# 06_USB_Type-C_DFP.net
KiCad netlist of a schematic drawn in Altium Designer
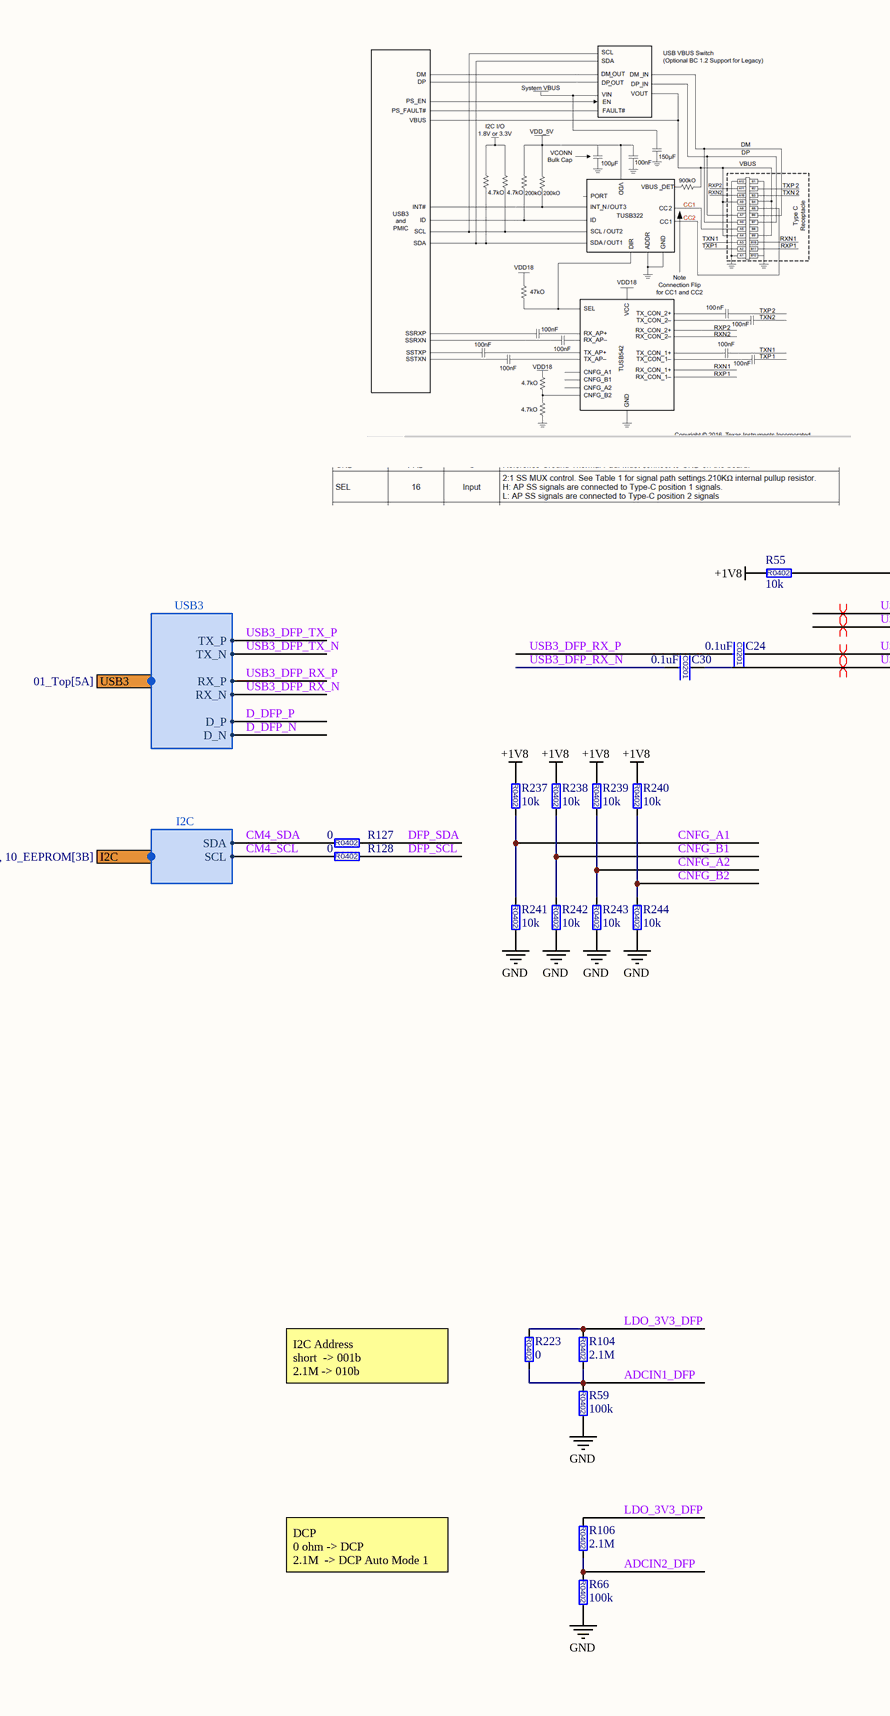
[diagram p0: 06_USB_Type-C_DFP.SchDoc, left]
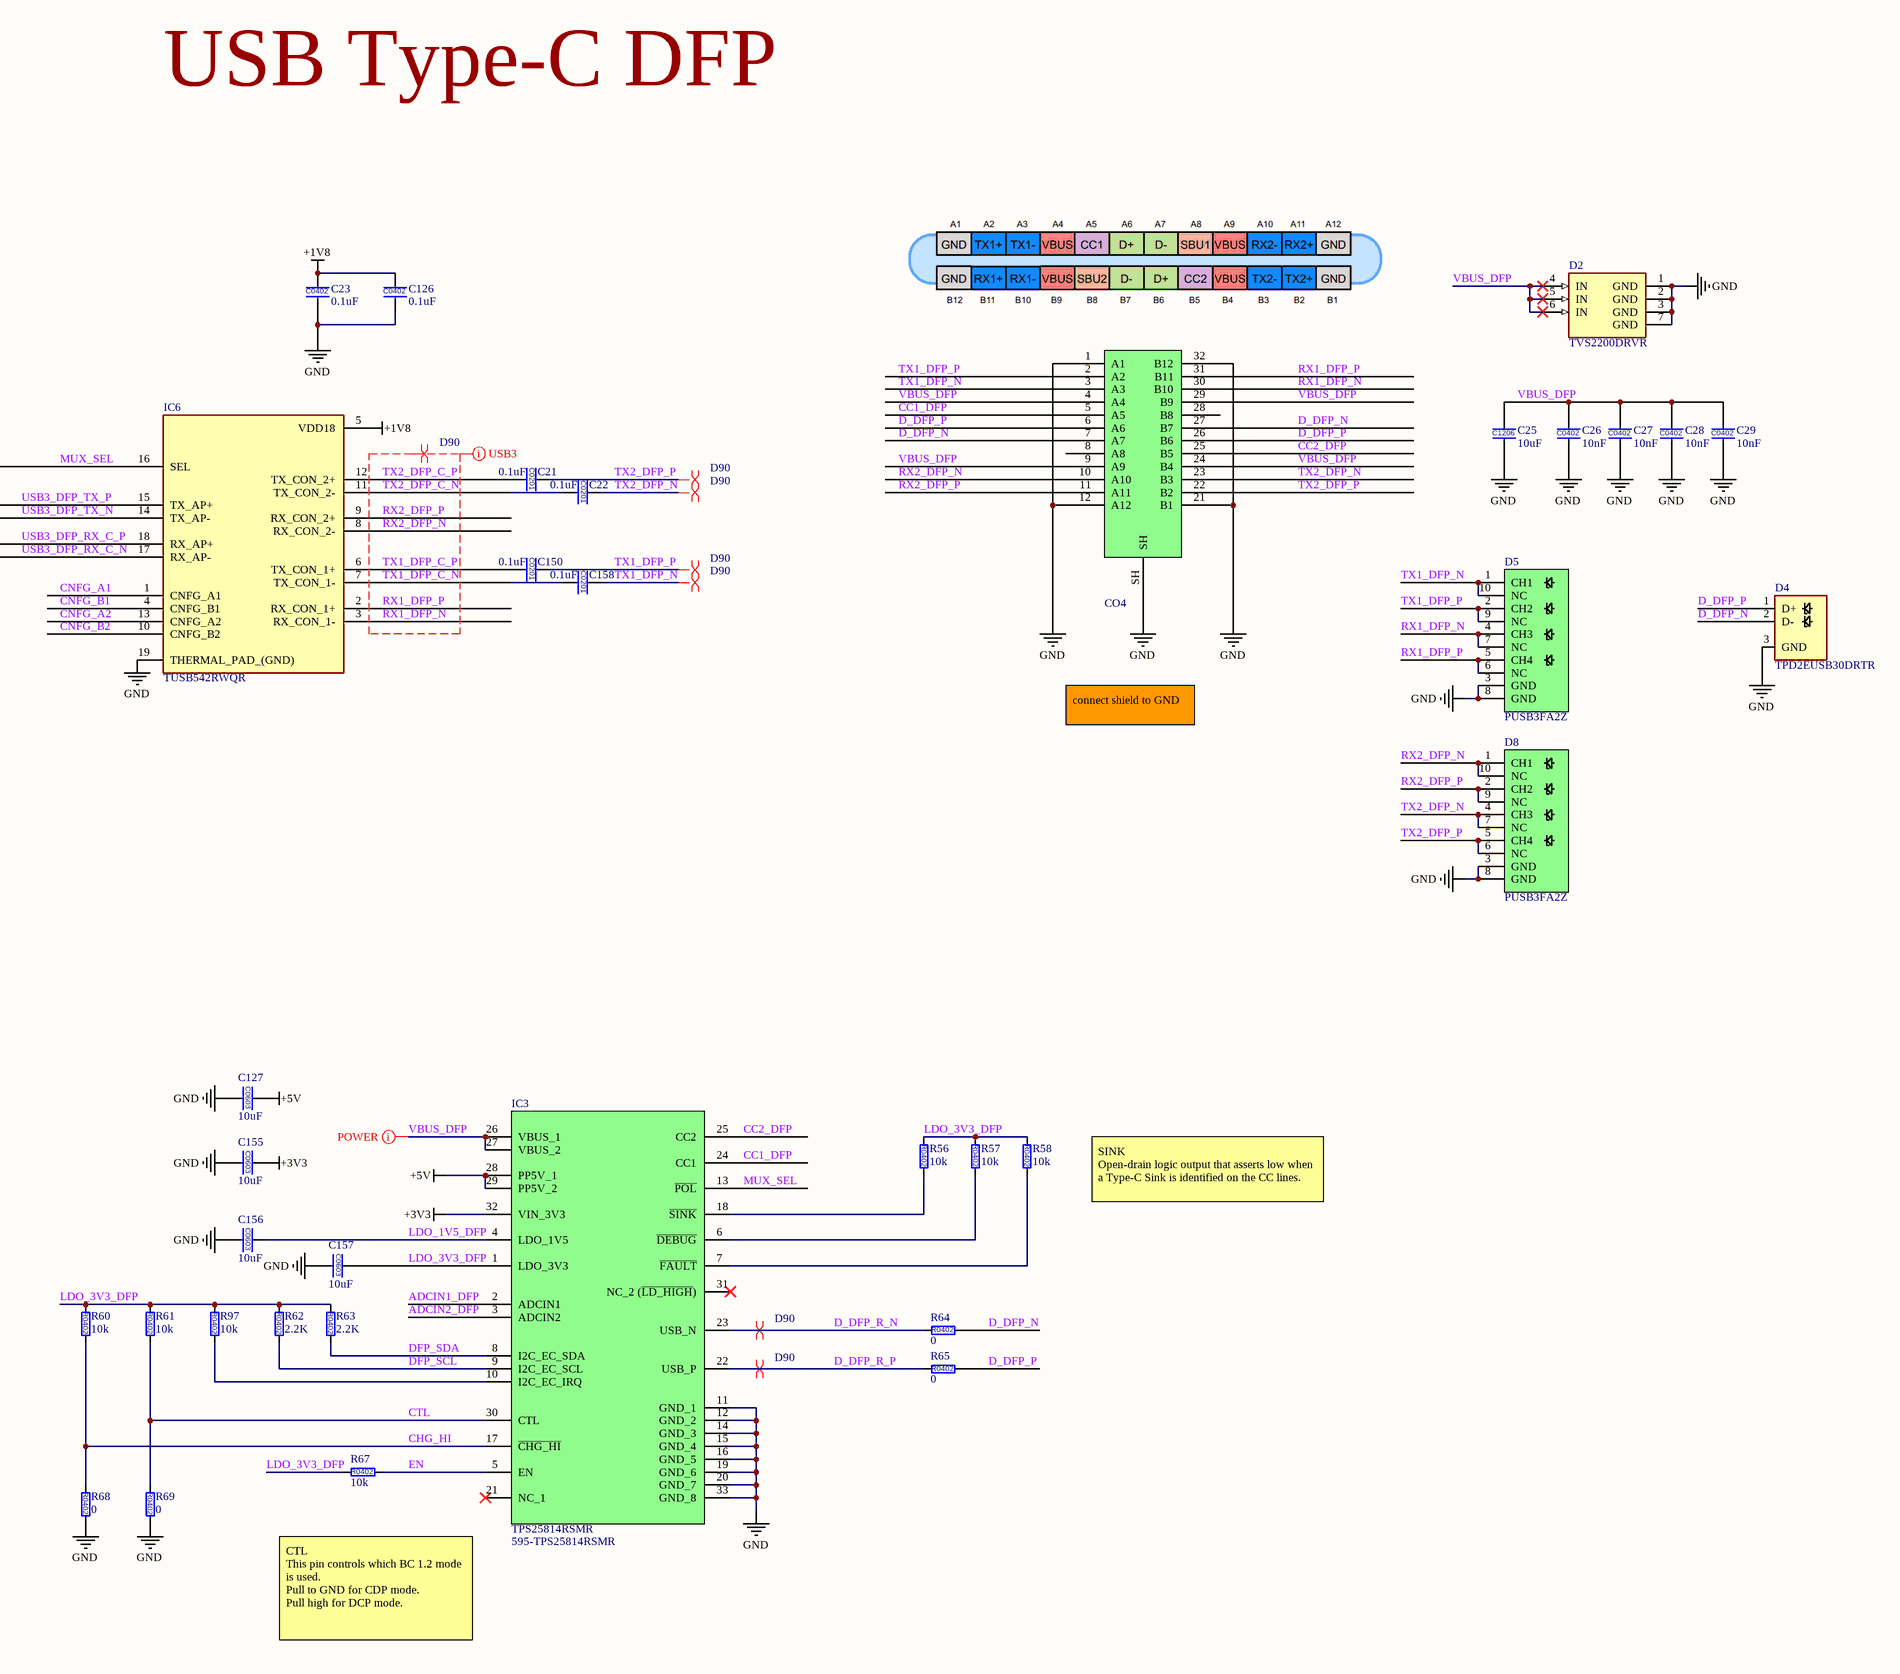
[diagram p1: 06_USB_Type-C_DFP.SchDoc, right]

(export (version "E")
  (design (tool "Eeschema 10.0.6"))
  (components
    (comp (ref "C21")
      (value "0.1uF")
      (footprint "C0201")
      (description "CAP CER  0.1uF 10% 6.3V X5R 0201")
      (fields
        (field (name "MANUFACTURER") "AVX Corporation")
        (field (name "MANUFACTURER PART NUMBER") "02016D104KAT")
      )
      (libsource (lib "Capacitor") (part "02016D104KAT"))
    )
    (comp (ref "C22")
      (value "0.1uF")
      (footprint "C0201")
      (description "CAP CER  0.1uF 10% 6.3V X5R 0201")
      (fields
        (field (name "MANUFACTURER") "AVX Corporation")
        (field (name "MANUFACTURER PART NUMBER") "02016D104KAT")
      )
      (libsource (lib "Capacitor") (part "02016D104KAT"))
    )
    (comp (ref "C23")
      (value "0.1uF")
      (footprint "C0402")
      (description "CAP CER  0.1uF 10% 25V X5R 0402")
      (fields
        (field (name "MANUFACTURER") "AVX Corporation")
        (field (name "MANUFACTURER PART NUMBER") "04023D104KAT2A")
      )
      (libsource (lib "Capacitor") (part "04023D104KAT2A"))
    )
    (comp (ref "C24")
      (value "0.1uF")
      (footprint "C0201")
      (description "CAP CER  0.1uF 10% 6.3V X5R 0201")
      (fields
        (field (name "MANUFACTURER") "AVX Corporation")
        (field (name "MANUFACTURER PART NUMBER") "02016D104KAT")
      )
      (libsource (lib "Capacitor") (part "02016D104KAT"))
    )
    (comp (ref "C25")
      (value "10uF")
      (footprint "C1206")
      (description "CAP CER  10uF 10% 50V X5R 1206")
      (fields
        (field (name "MANUFACTURER") "KYOCERA AVX")
        (field (name "MANUFACTURER PART NUMBER") "12065D106KAT4A")
      )
      (libsource (lib "Capacitor") (part "12065D106KAT4A"))
    )
    (comp (ref "C26")
      (value "10nF")
      (footprint "C0402")
      (description "CAP CER 10nF 5% 50V X7R 0402")
      (fields
        (field (name "MANUFACTURER") "KYOCERA AVX")
        (field (name "MANUFACTURER PART NUMBER") "04025C103JAT2A")
      )
      (libsource (lib "Capacitor") (part "04025C103JAT2A"))
    )
    (comp (ref "C27")
      (value "10nF")
      (footprint "C0402")
      (description "CAP CER 10nF 5% 50V X7R 0402")
      (fields
        (field (name "MANUFACTURER") "KYOCERA AVX")
        (field (name "MANUFACTURER PART NUMBER") "04025C103JAT2A")
      )
      (libsource (lib "Capacitor") (part "04025C103JAT2A"))
    )
    (comp (ref "C28")
      (value "10nF")
      (footprint "C0402")
      (description "CAP CER 10nF 5% 50V X7R 0402")
      (fields
        (field (name "MANUFACTURER") "KYOCERA AVX")
        (field (name "MANUFACTURER PART NUMBER") "04025C103JAT2A")
      )
      (libsource (lib "Capacitor") (part "04025C103JAT2A"))
    )
    (comp (ref "C29")
      (value "10nF")
      (footprint "C0402")
      (description "CAP CER 10nF 5% 50V X7R 0402")
      (fields
        (field (name "MANUFACTURER") "KYOCERA AVX")
        (field (name "MANUFACTURER PART NUMBER") "04025C103JAT2A")
      )
      (libsource (lib "Capacitor") (part "04025C103JAT2A"))
    )
    (comp (ref "C30")
      (value "0.1uF")
      (footprint "C0201")
      (description "CAP CER  0.1uF 10% 6.3V X5R 0201")
      (fields
        (field (name "MANUFACTURER") "AVX Corporation")
        (field (name "MANUFACTURER PART NUMBER") "02016D104KAT")
      )
      (libsource (lib "Capacitor") (part "02016D104KAT"))
    )
    (comp (ref "C126")
      (value "0.1uF")
      (footprint "C0402")
      (description "CAP CER  0.1uF 10% 25V X5R 0402")
      (fields
        (field (name "MANUFACTURER") "AVX Corporation")
        (field (name "MANUFACTURER PART NUMBER") "04023D104KAT2A")
      )
      (libsource (lib "Capacitor") (part "04023D104KAT2A"))
    )
    (comp (ref "C127")
      (value "10uF")
      (footprint "C0603")
      (description "CAP CER 10uF 10% 10V X5R 0603")
      (fields
        (field (name "MANUFACTURER") "KYOCERA AVX")
        (field (name "MANUFACTURER PART NUMBER") "0603ZD106KAT2A")
      )
      (libsource (lib "Capacitor") (part "0603ZD106KAT2A"))
    )
    (comp (ref "C150")
      (value "0.1uF")
      (footprint "C0201")
      (description "CAP CER  0.1uF 10% 6.3V X5R 0201")
      (fields
        (field (name "MANUFACTURER") "AVX Corporation")
        (field (name "MANUFACTURER PART NUMBER") "02016D104KAT")
      )
      (libsource (lib "Capacitor") (part "02016D104KAT"))
    )
    (comp (ref "C155")
      (value "10uF")
      (footprint "C0603")
      (description "CAP CER 10uF 10% 10V X5R 0603")
      (fields
        (field (name "MANUFACTURER") "KYOCERA AVX")
        (field (name "MANUFACTURER PART NUMBER") "0603ZD106KAT2A")
      )
      (libsource (lib "Capacitor") (part "0603ZD106KAT2A"))
    )
    (comp (ref "C156")
      (value "10uF")
      (footprint "C0603")
      (description "CAP CER 10uF 10% 10V X5R 0603")
      (fields
        (field (name "MANUFACTURER") "KYOCERA AVX")
        (field (name "MANUFACTURER PART NUMBER") "0603ZD106KAT2A")
      )
      (libsource (lib "Capacitor") (part "0603ZD106KAT2A"))
    )
    (comp (ref "C157")
      (value "10uF")
      (footprint "C0603")
      (description "CAP CER 10uF 10% 10V X5R 0603")
      (fields
        (field (name "MANUFACTURER") "KYOCERA AVX")
        (field (name "MANUFACTURER PART NUMBER") "0603ZD106KAT2A")
      )
      (libsource (lib "Capacitor") (part "0603ZD106KAT2A"))
    )
    (comp (ref "C158")
      (value "0.1uF")
      (footprint "C0201")
      (description "CAP CER  0.1uF 10% 6.3V X5R 0201")
      (fields
        (field (name "MANUFACTURER") "AVX Corporation")
        (field (name "MANUFACTURER PART NUMBER") "02016D104KAT")
      )
      (libsource (lib "Capacitor") (part "02016D104KAT"))
    )
    (comp (ref "CO4")
      (value "USB4070-30-C")
      (footprint "USB4070-30-C")
      (description "24 Position 20 VDC USB Type C Horizontal USB 3.1 Receptacle Connector")
      (fields
        (field (name "PART NUMBER") "CO0021")
        (field (name "MANUFACTURER") "Global Connector Technology")
      )
      (libsource (lib "new") (part "USB4070-30-C"))
    )
    (comp (ref "D2")
      (value "TVS2200DRVR")
      (footprint "TVS2200D_SON_6")
      (description "22-V flat-clamp surge protection device 6-WSON -40 to 125")
      (fields
        (field (name "OCTOPART") "https://octopart.com/tvs2200drvr-texas+instruments-88217346")
        (field (name "MANUFACTURER") "Texas Instruments")
      )
      (libsource (lib "new") (part "TVS2200DRVR"))
    )
    (comp (ref "D4")
      (value "TPD2EUSB30DRTR")
      (footprint "TPD2EUSB30DRTR_SOT-3")
      (fields (field (name "MANUFACTURER") "Texas Instruments"))
      (libsource (lib "TVS") (part "TPD2EUSB30DRTR"))
    )
    (comp (ref "D5")
      (value "PUSB3FA2Z")
      (footprint "PUSB3FA2Z_DFN_2510_10")
      (description "PUSB3FA2/SOT1176/XSON10")
      (fields (field (name "PART NUMBER") "DI0007") (field (name "MANUFACTURER") "Nexperia"))
      (libsource (lib "new") (part "PUSB3FA2Z"))
    )
    (comp (ref "D8")
      (value "PUSB3FA2Z")
      (footprint "PUSB3FA2Z_DFN_2510_10")
      (description "PUSB3FA2/SOT1176/XSON10")
      (fields (field (name "PART NUMBER") "DI0007") (field (name "MANUFACTURER") "Nexperia"))
      (libsource (lib "new") (part "PUSB3FA2Z"))
    )
    (comp (ref "IC3")
      (value "TPS25814RSMR")
      (footprint "TPS25814RSMR_VQFN_32")
      (description "USB Type-C® controller with integrated source power switch 32-VQFN -40 to 105")
      (fields
        (field (name "MOUSER PART NUMBER") "595-TPS25814RSMR")
        (field (name "MANUFACTURER") "Texas Instruments")
        (field (name "SUPPLIER PART NUMBER 1") "595-TPS25814RSMR")
      )
      (libsource (lib "new") (part "TPS25814RSMR"))
    )
    (comp (ref "IC6")
      (value "TUSB542RWQR")
      (footprint "TUSB542_X2QFN_18")
      (description "Integrated Circuit")
      (fields (field (name "MOUSER PART NUMBER") "595-TUSB542RWQR"))
      (libsource (lib "ic") (part "TUSB542RWQR"))
    )
    (comp (ref "R55")
      (value "10k")
      (footprint "R0402")
      (description "RES SMD 10K ohm 1% 1/16W R0402")
      (fields
        (field (name "MANUFACTURER") "Vishay")
        (field (name "MANUFACTURER PART NUMBER") "CRCW040210K0FK")
      )
      (libsource (lib "Resistor") (part "CRCW040210K0FK"))
    )
    (comp (ref "R56")
      (value "10k")
      (footprint "R0402")
      (description "RES SMD 10K ohm 1% 1/16W R0402")
      (fields
        (field (name "MANUFACTURER") "Vishay")
        (field (name "MANUFACTURER PART NUMBER") "CRCW040210K0FK")
      )
      (libsource (lib "Resistor") (part "CRCW040210K0FK"))
    )
    (comp (ref "R57")
      (value "10k")
      (footprint "R0402")
      (description "RES SMD 10K ohm 1% 1/16W R0402")
      (fields
        (field (name "MANUFACTURER") "Vishay")
        (field (name "MANUFACTURER PART NUMBER") "CRCW040210K0FK")
      )
      (libsource (lib "Resistor") (part "CRCW040210K0FK"))
    )
    (comp (ref "R58")
      (value "10k")
      (footprint "R0402")
      (description "RES SMD 10K ohm 1% 1/16W R0402")
      (fields
        (field (name "MANUFACTURER") "Vishay")
        (field (name "MANUFACTURER PART NUMBER") "CRCW040210K0FK")
      )
      (libsource (lib "Resistor") (part "CRCW040210K0FK"))
    )
    (comp (ref "R59")
      (value "100k")
      (footprint "R0402")
      (description "RES SMD 100K ohm 1% 1/16W R0402")
      (fields
        (field (name "MANUFACTURER") "Vishay")
        (field (name "MANUFACTURER PART NUMBER") "CRCW0402100KFKEDC")
      )
      (libsource (lib "Resistor") (part "CRCW0402100KFKEDC"))
    )
    (comp (ref "R60")
      (value "10k")
      (footprint "R0402")
      (description "RES SMD 10K ohm 1% 1/16W R0402")
      (fields
        (field (name "MANUFACTURER") "Vishay")
        (field (name "MANUFACTURER PART NUMBER") "CRCW040210K0FK")
      )
      (libsource (lib "Resistor") (part "CRCW040210K0FK"))
    )
    (comp (ref "R61")
      (value "10k")
      (footprint "R0402")
      (description "RES SMD 10K ohm 1% 1/16W R0402")
      (fields
        (field (name "MANUFACTURER") "Vishay")
        (field (name "MANUFACTURER PART NUMBER") "CRCW040210K0FK")
      )
      (libsource (lib "Resistor") (part "CRCW040210K0FK"))
    )
    (comp (ref "R62")
      (value "2.2K")
      (footprint "R0402")
      (description "RES SMD 2.2K ohm 1% 1/16W R0402")
      (fields
        (field (name "MANUFACTURER") "Vishay")
        (field (name "MANUFACTURER PART NUMBER") "CRCW04022K20FK")
      )
      (libsource (lib "Resistor") (part "CRCW04022K20FK"))
    )
    (comp (ref "R63")
      (value "2.2K")
      (footprint "R0402")
      (description "RES SMD 2.2K ohm 1% 1/16W R0402")
      (fields
        (field (name "MANUFACTURER") "Vishay")
        (field (name "MANUFACTURER PART NUMBER") "CRCW04022K20FK")
      )
      (libsource (lib "Resistor") (part "CRCW04022K20FK"))
    )
    (comp (ref "R64")
      (value "0")
      (footprint "R0402")
      (description "RES SMD 0 ohm 1/16W R0402")
      (fields
        (field (name "MANUFACTURER") "Vishay Dale")
        (field (name "MANUFACTURER PART NUMBER") "CRCW04020000Z0")
      )
      (libsource (lib "Resistor") (part "CRCW04020000Z0"))
    )
    (comp (ref "R65")
      (value "0")
      (footprint "R0402")
      (description "RES SMD 0 ohm 1/16W R0402")
      (fields
        (field (name "MANUFACTURER") "Vishay Dale")
        (field (name "MANUFACTURER PART NUMBER") "CRCW04020000Z0")
      )
      (libsource (lib "Resistor") (part "CRCW04020000Z0"))
    )
    (comp (ref "R66")
      (value "100k")
      (footprint "R0402")
      (description "RES SMD 100K ohm 1% 1/16W R0402")
      (fields
        (field (name "MANUFACTURER") "Vishay")
        (field (name "MANUFACTURER PART NUMBER") "CRCW0402100KFKEDC")
      )
      (libsource (lib "Resistor") (part "CRCW0402100KFKEDC"))
    )
    (comp (ref "R67")
      (value "10k")
      (footprint "R0402")
      (description "RES SMD 10K ohm 1% 1/16W R0402")
      (fields
        (field (name "MANUFACTURER") "Vishay")
        (field (name "MANUFACTURER PART NUMBER") "CRCW040210K0FK")
      )
      (libsource (lib "Resistor") (part "CRCW040210K0FK"))
    )
    (comp (ref "R68")
      (value "0")
      (footprint "R0402")
      (description "RES SMD 0 ohm 1/16W R0402")
      (fields
        (field (name "MANUFACTURER") "Vishay Dale")
        (field (name "MANUFACTURER PART NUMBER") "CRCW04020000Z0")
      )
      (libsource (lib "Resistor") (part "CRCW04020000Z0"))
    )
    (comp (ref "R69")
      (value "0")
      (footprint "R0402")
      (description "RES SMD 0 ohm 1/16W R0402")
      (fields
        (field (name "MANUFACTURER") "Vishay Dale")
        (field (name "MANUFACTURER PART NUMBER") "CRCW04020000Z0")
      )
      (libsource (lib "Resistor") (part "CRCW04020000Z0"))
    )
    (comp (ref "R97")
      (value "10k")
      (footprint "R0402")
      (description "RES SMD 10K ohm 1% 1/16W R0402")
      (fields
        (field (name "MANUFACTURER") "Vishay")
        (field (name "MANUFACTURER PART NUMBER") "CRCW040210K0FK")
      )
      (libsource (lib "Resistor") (part "CRCW040210K0FK"))
    )
    (comp (ref "R104")
      (value "2.1M")
      (footprint "R0402")
      (description "RES SMD 2.1M ohm 1% 1/16W R0402")
      (fields
        (field (name "MANUFACTURER") "Vishay")
        (field (name "MANUFACTURER PART NUMBER") "CRCW04022M10FKED")
      )
      (libsource (lib "Resistor") (part "CRCW04022M10FKED"))
    )
    (comp (ref "R106")
      (value "2.1M")
      (footprint "R0402")
      (description "RES SMD 2.1M ohm 1% 1/16W R0402")
      (fields
        (field (name "MANUFACTURER") "Vishay")
        (field (name "MANUFACTURER PART NUMBER") "CRCW04022M10FKED")
      )
      (libsource (lib "Resistor") (part "CRCW04022M10FKED"))
    )
    (comp (ref "R127")
      (value "0")
      (footprint "R0402")
      (description "RES SMD 0 ohm 1/16W R0402")
      (fields
        (field (name "MANUFACTURER") "Vishay Dale")
        (field (name "MANUFACTURER PART NUMBER") "CRCW04020000Z0")
      )
      (libsource (lib "Resistor") (part "CRCW04020000Z0"))
    )
    (comp (ref "R128")
      (value "0")
      (footprint "R0402")
      (description "RES SMD 0 ohm 1/16W R0402")
      (fields
        (field (name "MANUFACTURER") "Vishay Dale")
        (field (name "MANUFACTURER PART NUMBER") "CRCW04020000Z0")
      )
      (libsource (lib "Resistor") (part "CRCW04020000Z0"))
    )
    (comp (ref "R223")
      (value "0")
      (footprint "R0402")
      (description "RES SMD 0 ohm 1/16W R0402")
      (fields
        (field (name "MANUFACTURER") "Vishay Dale")
        (field (name "MANUFACTURER PART NUMBER") "CRCW04020000Z0")
      )
      (libsource (lib "Resistor") (part "CRCW04020000Z0"))
    )
    (comp (ref "R237")
      (value "10k")
      (footprint "R0402")
      (description "RES SMD 10K ohm 1% 1/16W R0402")
      (fields
        (field (name "MANUFACTURER") "Vishay")
        (field (name "MANUFACTURER PART NUMBER") "CRCW040210K0FK")
      )
      (libsource (lib "Resistor") (part "CRCW040210K0FK"))
    )
    (comp (ref "R238")
      (value "10k")
      (footprint "R0402")
      (description "RES SMD 10K ohm 1% 1/16W R0402")
      (fields
        (field (name "MANUFACTURER") "Vishay")
        (field (name "MANUFACTURER PART NUMBER") "CRCW040210K0FK")
      )
      (libsource (lib "Resistor") (part "CRCW040210K0FK"))
    )
    (comp (ref "R239")
      (value "10k")
      (footprint "R0402")
      (description "RES SMD 10K ohm 1% 1/16W R0402")
      (fields
        (field (name "MANUFACTURER") "Vishay")
        (field (name "MANUFACTURER PART NUMBER") "CRCW040210K0FK")
      )
      (libsource (lib "Resistor") (part "CRCW040210K0FK"))
    )
    (comp (ref "R240")
      (value "10k")
      (footprint "R0402")
      (description "RES SMD 10K ohm 1% 1/16W R0402")
      (fields
        (field (name "MANUFACTURER") "Vishay")
        (field (name "MANUFACTURER PART NUMBER") "CRCW040210K0FK")
      )
      (libsource (lib "Resistor") (part "CRCW040210K0FK"))
    )
    (comp (ref "R241")
      (value "10k")
      (footprint "R0402")
      (description "RES SMD 10K ohm 1% 1/16W R0402")
      (fields
        (field (name "MANUFACTURER") "Vishay")
        (field (name "MANUFACTURER PART NUMBER") "CRCW040210K0FK")
      )
      (libsource (lib "Resistor") (part "CRCW040210K0FK"))
    )
    (comp (ref "R242")
      (value "10k")
      (footprint "R0402")
      (description "RES SMD 10K ohm 1% 1/16W R0402")
      (fields
        (field (name "MANUFACTURER") "Vishay")
        (field (name "MANUFACTURER PART NUMBER") "CRCW040210K0FK")
      )
      (libsource (lib "Resistor") (part "CRCW040210K0FK"))
    )
    (comp (ref "R243")
      (value "10k")
      (footprint "R0402")
      (description "RES SMD 10K ohm 1% 1/16W R0402")
      (fields
        (field (name "MANUFACTURER") "Vishay")
        (field (name "MANUFACTURER PART NUMBER") "CRCW040210K0FK")
      )
      (libsource (lib "Resistor") (part "CRCW040210K0FK"))
    )
    (comp (ref "R244")
      (value "10k")
      (footprint "R0402")
      (description "RES SMD 10K ohm 1% 1/16W R0402")
      (fields
        (field (name "MANUFACTURER") "Vishay")
        (field (name "MANUFACTURER PART NUMBER") "CRCW040210K0FK")
      )
      (libsource (lib "Resistor") (part "CRCW040210K0FK"))
    )
  )
  (nets
    (net (code "3") (name "+1V8") (class "Default")
      (node (ref "C126") (pin "1") (pinfunction "1_1") (pintype "passive"))
      (node (ref "C23") (pin "1") (pinfunction "1_1") (pintype "passive"))
      (node (ref "IC6") (pin "5") (pinfunction "VDD18_5") (pintype "passive"))
      (node (ref "R237") (pin "1") (pinfunction "1_1") (pintype "passive"))
      (node (ref "R238") (pin "1") (pinfunction "1_1") (pintype "passive"))
      (node (ref "R239") (pin "1") (pinfunction "1_1") (pintype "passive"))
      (node (ref "R240") (pin "1") (pinfunction "1_1") (pintype "passive"))
      (node (ref "R55") (pin "1") (pinfunction "1_1") (pintype "passive"))
    )
    (net (code "4") (name "+3V3") (class "Default")
      (node (ref "C155") (pin "1") (pinfunction "1_1") (pintype "passive"))
      (node (ref "IC3") (pin "32") (pinfunction "VIN_3V3_32") (pintype "passive"))
    )
    (net (code "5") (name "+5V") (class "Default")
      (node (ref "C127") (pin "1") (pinfunction "1_1") (pintype "passive"))
      (node (ref "IC3") (pin "28") (pinfunction "PP5V_1_28") (pintype "passive"))
      (node (ref "IC3") (pin "29") (pinfunction "PP5V_2_29") (pintype "passive"))
    )
    (net (code "6") (name "/ADCIN1_DFP") (class "Default")
      (node (ref "IC3") (pin "2") (pinfunction "ADCIN1_2") (pintype "passive"))
      (node (ref "R104") (pin "2") (pinfunction "2_2") (pintype "passive"))
      (node (ref "R223") (pin "2") (pinfunction "2_2") (pintype "passive"))
      (node (ref "R59") (pin "1") (pinfunction "1_1") (pintype "passive"))
    )
    (net (code "7") (name "/ADCIN2_DFP") (class "Default")
      (node (ref "IC3") (pin "3") (pinfunction "ADCIN2_3") (pintype "passive"))
      (node (ref "R106") (pin "2") (pinfunction "2_2") (pintype "passive"))
      (node (ref "R66") (pin "1") (pinfunction "1_1") (pintype "passive"))
    )
    (net (code "8") (name "/CC1_DFP") (class "Default")
      (node (ref "CO4") (pin "5") (pinfunction "A5_5") (pintype "passive"))
      (node (ref "IC3") (pin "24") (pinfunction "CC1_24") (pintype "passive"))
    )
    (net (code "9") (name "/CC2_DFP") (class "Default")
      (node (ref "CO4") (pin "25") (pinfunction "B5_25") (pintype "passive"))
      (node (ref "IC3") (pin "25") (pinfunction "CC2_25") (pintype "passive"))
    )
    (net (code "10") (name "/CHG_HI") (class "Default")
      (node (ref "IC3") (pin "17") (pinfunction "~{CHG_HI}_17") (pintype "passive"))
      (node (ref "R60") (pin "2") (pinfunction "2_2") (pintype "passive"))
      (node (ref "R68") (pin "1") (pinfunction "1_1") (pintype "passive"))
    )
    (net (code "11") (name "/CM4_SCL") (class "Default")
      (node (ref "R128") (pin "1") (pinfunction "1_1") (pintype "passive"))
    )
    (net (code "12") (name "/CM4_SDA") (class "Default")
      (node (ref "R127") (pin "1") (pinfunction "1_1") (pintype "passive"))
    )
    (net (code "13") (name "/CNFG_A1") (class "Default")
      (node (ref "IC6") (pin "1") (pinfunction "CNFG_A1_1") (pintype "passive"))
      (node (ref "R237") (pin "2") (pinfunction "2_2") (pintype "passive"))
      (node (ref "R241") (pin "1") (pinfunction "1_1") (pintype "passive"))
    )
    (net (code "14") (name "/CNFG_A2") (class "Default")
      (node (ref "IC6") (pin "13") (pinfunction "CNFG_A2_13") (pintype "passive"))
      (node (ref "R239") (pin "2") (pinfunction "2_2") (pintype "passive"))
      (node (ref "R243") (pin "1") (pinfunction "1_1") (pintype "passive"))
    )
    (net (code "15") (name "/CNFG_B1") (class "Default")
      (node (ref "IC6") (pin "4") (pinfunction "CNFG_B1_4") (pintype "passive"))
      (node (ref "R238") (pin "2") (pinfunction "2_2") (pintype "passive"))
      (node (ref "R242") (pin "1") (pinfunction "1_1") (pintype "passive"))
    )
    (net (code "16") (name "/CNFG_B2") (class "Default")
      (node (ref "IC6") (pin "10") (pinfunction "CNFG_B2_10") (pintype "passive"))
      (node (ref "R240") (pin "2") (pinfunction "2_2") (pintype "passive"))
      (node (ref "R244") (pin "1") (pinfunction "1_1") (pintype "passive"))
    )
    (net (code "17") (name "/CTL") (class "Default")
      (node (ref "IC3") (pin "30") (pinfunction "CTL_30") (pintype "passive"))
      (node (ref "R61") (pin "2") (pinfunction "2_2") (pintype "passive"))
      (node (ref "R69") (pin "1") (pinfunction "1_1") (pintype "passive"))
    )
    (net (code "18") (name "/DFP_SCL") (class "Default")
      (node (ref "IC3") (pin "9") (pinfunction "I2C_EC_SCL_9") (pintype "passive"))
      (node (ref "R128") (pin "2") (pinfunction "2_2") (pintype "passive"))
      (node (ref "R62") (pin "2") (pinfunction "2_2") (pintype "passive"))
    )
    (net (code "19") (name "/DFP_SDA") (class "Default")
      (node (ref "IC3") (pin "8") (pinfunction "I2C_EC_SDA_8") (pintype "passive"))
      (node (ref "R127") (pin "2") (pinfunction "2_2") (pintype "passive"))
      (node (ref "R63") (pin "2") (pinfunction "2_2") (pintype "passive"))
    )
    (net (code "20") (name "/D_DFP_N") (class "Default")
      (node (ref "CO4") (pin "27") (pinfunction "B7_27") (pintype "passive"))
      (node (ref "CO4") (pin "7") (pinfunction "A7_7") (pintype "passive"))
      (node (ref "D4") (pin "2") (pinfunction "D-_2") (pintype "passive"))
      (node (ref "R64") (pin "2") (pinfunction "2_2") (pintype "passive"))
    )
    (net (code "21") (name "/D_DFP_P") (class "Default")
      (node (ref "CO4") (pin "26") (pinfunction "B6_26") (pintype "passive"))
      (node (ref "CO4") (pin "6") (pinfunction "A6_6") (pintype "passive"))
      (node (ref "D4") (pin "1") (pinfunction "D+_1") (pintype "passive"))
      (node (ref "R65") (pin "2") (pinfunction "2_2") (pintype "passive"))
    )
    (net (code "22") (name "/D_DFP_R_N") (class "Default")
      (node (ref "IC3") (pin "23") (pinfunction "USB_N_23") (pintype "passive"))
      (node (ref "R64") (pin "1") (pinfunction "1_1") (pintype "passive"))
    )
    (net (code "23") (name "/D_DFP_R_P") (class "Default")
      (node (ref "IC3") (pin "22") (pinfunction "USB_P_22") (pintype "passive"))
      (node (ref "R65") (pin "1") (pinfunction "1_1") (pintype "passive"))
    )
    (net (code "24") (name "/EN") (class "Default")
      (node (ref "IC3") (pin "5") (pinfunction "EN_5") (pintype "passive"))
      (node (ref "R67") (pin "2") (pinfunction "2_2") (pintype "passive"))
    )
    (net (code "25") (name "/LDO_1V5_DFP") (class "Default")
      (node (ref "C156") (pin "1") (pinfunction "1_1") (pintype "passive"))
      (node (ref "IC3") (pin "4") (pinfunction "LDO_1V5_4") (pintype "passive"))
    )
    (net (code "26") (name "/LDO_3V3_DFP") (class "Default")
      (node (ref "C157") (pin "1") (pinfunction "1_1") (pintype "passive"))
      (node (ref "IC3") (pin "1") (pinfunction "LDO_3V3_1") (pintype "passive"))
      (node (ref "R104") (pin "1") (pinfunction "1_1") (pintype "passive"))
      (node (ref "R106") (pin "1") (pinfunction "1_1") (pintype "passive"))
      (node (ref "R223") (pin "1") (pinfunction "1_1") (pintype "passive"))
      (node (ref "R56") (pin "1") (pinfunction "1_1") (pintype "passive"))
      (node (ref "R57") (pin "1") (pinfunction "1_1") (pintype "passive"))
      (node (ref "R58") (pin "1") (pinfunction "1_1") (pintype "passive"))
      (node (ref "R60") (pin "1") (pinfunction "1_1") (pintype "passive"))
      (node (ref "R61") (pin "1") (pinfunction "1_1") (pintype "passive"))
      (node (ref "R62") (pin "1") (pinfunction "1_1") (pintype "passive"))
      (node (ref "R63") (pin "1") (pinfunction "1_1") (pintype "passive"))
      (node (ref "R67") (pin "1") (pinfunction "1_1") (pintype "passive"))
      (node (ref "R97") (pin "1") (pinfunction "1_1") (pintype "passive"))
    )
    (net (code "27") (name "/MUX_SEL") (class "Default")
      (node (ref "IC3") (pin "13") (pinfunction "~{POL}_13") (pintype "passive"))
      (node (ref "IC6") (pin "16") (pinfunction "SEL_16") (pintype "passive"))
      (node (ref "R55") (pin "2") (pinfunction "2_2") (pintype "passive"))
    )
    (net (code "28") (name "/RX1_DFP_N") (class "Default")
      (node (ref "CO4") (pin "30") (pinfunction "B10_30") (pintype "passive"))
      (node (ref "D5") (pin "4") (pinfunction "CH3_4") (pintype "passive"))
      (node (ref "D5") (pin "7") (pinfunction "NC_7") (pintype "passive"))
      (node (ref "IC6") (pin "3") (pinfunction "RX_CON_1-_3") (pintype "passive"))
    )
    (net (code "29") (name "/RX1_DFP_P") (class "Default")
      (node (ref "CO4") (pin "31") (pinfunction "B11_31") (pintype "passive"))
      (node (ref "D5") (pin "5") (pinfunction "CH4_5") (pintype "passive"))
      (node (ref "D5") (pin "6") (pinfunction "NC_6") (pintype "passive"))
      (node (ref "IC6") (pin "2") (pinfunction "RX_CON_1+_2") (pintype "passive"))
    )
    (net (code "30") (name "/RX2_DFP_N") (class "Default")
      (node (ref "CO4") (pin "10") (pinfunction "A10_10") (pintype "passive"))
      (node (ref "D8") (pin "1") (pinfunction "CH1_1") (pintype "passive"))
      (node (ref "D8") (pin "10") (pinfunction "NC_10") (pintype "passive"))
      (node (ref "IC6") (pin "8") (pinfunction "RX_CON_2-_8") (pintype "passive"))
    )
    (net (code "31") (name "/RX2_DFP_P") (class "Default")
      (node (ref "CO4") (pin "11") (pinfunction "A11_11") (pintype "passive"))
      (node (ref "D8") (pin "2") (pinfunction "CH2_2") (pintype "passive"))
      (node (ref "D8") (pin "9") (pinfunction "NC_9") (pintype "passive"))
      (node (ref "IC6") (pin "9") (pinfunction "RX_CON_2+_9") (pintype "passive"))
    )
    (net (code "32") (name "/TX1_DFP_C_N") (class "Default")
      (node (ref "C158") (pin "2") (pinfunction "2_2") (pintype "passive"))
      (node (ref "IC6") (pin "7") (pinfunction "TX_CON_1-_7") (pintype "passive"))
    )
    (net (code "33") (name "/TX1_DFP_C_P") (class "Default")
      (node (ref "C150") (pin "2") (pinfunction "2_2") (pintype "passive"))
      (node (ref "IC6") (pin "6") (pinfunction "TX_CON_1+_6") (pintype "passive"))
    )
    (net (code "34") (name "/TX1_DFP_N") (class "Default")
      (node (ref "C158") (pin "1") (pinfunction "1_1") (pintype "passive"))
      (node (ref "CO4") (pin "3") (pinfunction "A3_3") (pintype "passive"))
      (node (ref "D5") (pin "1") (pinfunction "CH1_1") (pintype "passive"))
      (node (ref "D5") (pin "10") (pinfunction "NC_10") (pintype "passive"))
    )
    (net (code "35") (name "/TX1_DFP_P") (class "Default")
      (node (ref "C150") (pin "1") (pinfunction "1_1") (pintype "passive"))
      (node (ref "CO4") (pin "2") (pinfunction "A2_2") (pintype "passive"))
      (node (ref "D5") (pin "2") (pinfunction "CH2_2") (pintype "passive"))
      (node (ref "D5") (pin "9") (pinfunction "NC_9") (pintype "passive"))
    )
    (net (code "36") (name "/TX2_DFP_C_N") (class "Default")
      (node (ref "C22") (pin "2") (pinfunction "2_2") (pintype "passive"))
      (node (ref "IC6") (pin "11") (pinfunction "TX_CON_2-_11") (pintype "passive"))
    )
    (net (code "37") (name "/TX2_DFP_C_P") (class "Default")
      (node (ref "C21") (pin "2") (pinfunction "2_2") (pintype "passive"))
      (node (ref "IC6") (pin "12") (pinfunction "TX_CON_2+_12") (pintype "passive"))
    )
    (net (code "38") (name "/TX2_DFP_N") (class "Default")
      (node (ref "C22") (pin "1") (pinfunction "1_1") (pintype "passive"))
      (node (ref "CO4") (pin "23") (pinfunction "B3_23") (pintype "passive"))
      (node (ref "D8") (pin "4") (pinfunction "CH3_4") (pintype "passive"))
      (node (ref "D8") (pin "7") (pinfunction "NC_7") (pintype "passive"))
    )
    (net (code "39") (name "/TX2_DFP_P") (class "Default")
      (node (ref "C21") (pin "1") (pinfunction "1_1") (pintype "passive"))
      (node (ref "CO4") (pin "22") (pinfunction "B2_22") (pintype "passive"))
      (node (ref "D8") (pin "5") (pinfunction "CH4_5") (pintype "passive"))
      (node (ref "D8") (pin "6") (pinfunction "NC_6") (pintype "passive"))
    )
    (net (code "40") (name "/USB3_DFP_RX_C_N") (class "Default")
      (node (ref "C30") (pin "1") (pinfunction "1_1") (pintype "passive"))
      (node (ref "IC6") (pin "17") (pinfunction "RX_AP-_17") (pintype "passive"))
    )
    (net (code "41") (name "/USB3_DFP_RX_C_P") (class "Default")
      (node (ref "C24") (pin "1") (pinfunction "1_1") (pintype "passive"))
      (node (ref "IC6") (pin "18") (pinfunction "RX_AP+_18") (pintype "passive"))
    )
    (net (code "42") (name "/USB3_DFP_RX_N") (class "Default")
      (node (ref "C30") (pin "2") (pinfunction "2_2") (pintype "passive"))
    )
    (net (code "43") (name "/USB3_DFP_RX_P") (class "Default")
      (node (ref "C24") (pin "2") (pinfunction "2_2") (pintype "passive"))
    )
    (net (code "44") (name "/USB3_DFP_TX_N") (class "Default")
      (node (ref "IC6") (pin "14") (pinfunction "TX_AP-_14") (pintype "passive"))
    )
    (net (code "45") (name "/USB3_DFP_TX_P") (class "Default")
      (node (ref "IC6") (pin "15") (pinfunction "TX_AP+_15") (pintype "passive"))
    )
    (net (code "46") (name "/VBUS_DFP") (class "Default")
      (node (ref "C25") (pin "1") (pinfunction "1_1") (pintype "passive"))
      (node (ref "C26") (pin "1") (pinfunction "1_1") (pintype "passive"))
      (node (ref "C27") (pin "1") (pinfunction "1_1") (pintype "passive"))
      (node (ref "C28") (pin "1") (pinfunction "1_1") (pintype "passive"))
      (node (ref "C29") (pin "1") (pinfunction "1_1") (pintype "passive"))
      (node (ref "CO4") (pin "24") (pinfunction "B4_24") (pintype "passive"))
      (node (ref "CO4") (pin "29") (pinfunction "B9_29") (pintype "passive"))
      (node (ref "CO4") (pin "4") (pinfunction "A4_4") (pintype "passive"))
      (node (ref "CO4") (pin "9") (pinfunction "A9_9") (pintype "passive"))
      (node (ref "D2") (pin "4") (pinfunction "IN_4") (pintype "input"))
      (node (ref "D2") (pin "5") (pinfunction "IN_5") (pintype "input"))
      (node (ref "D2") (pin "6") (pinfunction "IN_6") (pintype "input"))
      (node (ref "IC3") (pin "26") (pinfunction "VBUS_1_26") (pintype "passive"))
      (node (ref "IC3") (pin "27") (pinfunction "VBUS_2_27") (pintype "passive"))
    )
    (net (code "49") (name "GND") (class "Default")
      (node (ref "C126") (pin "2") (pinfunction "2_2") (pintype "passive"))
      (node (ref "C127") (pin "2") (pinfunction "2_2") (pintype "passive"))
      (node (ref "C155") (pin "2") (pinfunction "2_2") (pintype "passive"))
      (node (ref "C156") (pin "2") (pinfunction "2_2") (pintype "passive"))
      (node (ref "C157") (pin "2") (pinfunction "2_2") (pintype "passive"))
      (node (ref "C23") (pin "2") (pinfunction "2_2") (pintype "passive"))
      (node (ref "C25") (pin "2") (pinfunction "2_2") (pintype "passive"))
      (node (ref "C26") (pin "2") (pinfunction "2_2") (pintype "passive"))
      (node (ref "C27") (pin "2") (pinfunction "2_2") (pintype "passive"))
      (node (ref "C28") (pin "2") (pinfunction "2_2") (pintype "passive"))
      (node (ref "C29") (pin "2") (pinfunction "2_2") (pintype "passive"))
      (node (ref "CO4") (pin "1") (pinfunction "A1_1") (pintype "passive"))
      (node (ref "CO4") (pin "12") (pinfunction "A12_12") (pintype "passive"))
      (node (ref "CO4") (pin "21") (pinfunction "B1_21") (pintype "passive"))
      (node (ref "CO4") (pin "32") (pinfunction "B12_32") (pintype "passive"))
      (node (ref "CO4") (pin "SH") (pinfunction "SH_SH") (pintype "power_in"))
      (node (ref "D2") (pin "1") (pinfunction "GND_1") (pintype "power_in"))
      (node (ref "D2") (pin "2") (pinfunction "GND_2") (pintype "power_in"))
      (node (ref "D2") (pin "3") (pinfunction "GND_3") (pintype "power_in"))
      (node (ref "D2") (pin "7") (pinfunction "GND_7") (pintype "power_in"))
      (node (ref "D4") (pin "3") (pinfunction "GND_3") (pintype "power_in"))
      (node (ref "D5") (pin "3") (pinfunction "GND_3") (pintype "passive"))
      (node (ref "D5") (pin "8") (pinfunction "GND_8") (pintype "passive"))
      (node (ref "D8") (pin "3") (pinfunction "GND_3") (pintype "passive"))
      (node (ref "D8") (pin "8") (pinfunction "GND_8") (pintype "passive"))
      (node (ref "IC3") (pin "11") (pinfunction "GND_1_11") (pintype "passive"))
      (node (ref "IC3") (pin "12") (pinfunction "GND_2_12") (pintype "passive"))
      (node (ref "IC3") (pin "14") (pinfunction "GND_3_14") (pintype "passive"))
      (node (ref "IC3") (pin "15") (pinfunction "GND_4_15") (pintype "passive"))
      (node (ref "IC3") (pin "16") (pinfunction "GND_5_16") (pintype "passive"))
      (node (ref "IC3") (pin "19") (pinfunction "GND_6_19") (pintype "passive"))
      (node (ref "IC3") (pin "20") (pinfunction "GND_7_20") (pintype "passive"))
      (node (ref "IC3") (pin "33") (pinfunction "GND_8_33") (pintype "passive"))
      (node (ref "IC6") (pin "19") (pinfunction "THERMAL_PAD_(GND)_19") (pintype "passive"))
      (node (ref "R241") (pin "2") (pinfunction "2_2") (pintype "passive"))
      (node (ref "R242") (pin "2") (pinfunction "2_2") (pintype "passive"))
      (node (ref "R243") (pin "2") (pinfunction "2_2") (pintype "passive"))
      (node (ref "R244") (pin "2") (pinfunction "2_2") (pintype "passive"))
      (node (ref "R59") (pin "2") (pinfunction "2_2") (pintype "passive"))
      (node (ref "R66") (pin "2") (pinfunction "2_2") (pintype "passive"))
      (node (ref "R68") (pin "2") (pinfunction "2_2") (pintype "passive"))
      (node (ref "R69") (pin "2") (pinfunction "2_2") (pintype "passive"))
    )
    (net (code "50") (name "Net-(IC3-I2C_EC_IRQ)") (class "Default")
      (node (ref "IC3") (pin "10") (pinfunction "I2C_EC_IRQ_10") (pintype "passive"))
      (node (ref "R97") (pin "2") (pinfunction "2_2") (pintype "passive"))
    )
    (net (code "51") (name "Net-(IC3-~{DEBUG})") (class "Default")
      (node (ref "IC3") (pin "6") (pinfunction "~{DEBUG}_6") (pintype "passive"))
      (node (ref "R57") (pin "2") (pinfunction "2_2") (pintype "passive"))
    )
    (net (code "52") (name "Net-(IC3-~{FAULT})") (class "Default")
      (node (ref "IC3") (pin "7") (pinfunction "~{FAULT}_7") (pintype "passive"))
      (node (ref "R58") (pin "2") (pinfunction "2_2") (pintype "passive"))
    )
    (net (code "53") (name "Net-(IC3-~{SINK})") (class "Default")
      (node (ref "IC3") (pin "18") (pinfunction "~{SINK}_18") (pintype "passive"))
      (node (ref "R56") (pin "2") (pinfunction "2_2") (pintype "passive"))
    )
    (net (code "54") (name "unconnected-(CO4-A8-Pad8)") (class "Default")
      (node (ref "CO4") (pin "8") (pinfunction "A8_8") (pintype "passive"))
    )
    (net (code "55") (name "unconnected-(CO4-B8-Pad28)") (class "Default")
      (node (ref "CO4") (pin "28") (pinfunction "B8_28") (pintype "passive"))
    )
    (net (code "56") (name "unconnected-(IC3-NC_1-Pad21)") (class "Default")
      (node (ref "IC3") (pin "21") (pinfunction "NC_1_21") (pintype "passive+no_connect"))
    )
    (net (code "57") (name "unconnected-(IC3-NC_2_(~{LD_HIGH})-Pad31)") (class "Default")
      (node (ref "IC3") (pin "31") (pinfunction "NC_2_(~{LD_HIGH})_31") (pintype "passive+no_connect"))
    )
  )
)
